# TwoLayerMotorDriver.net
KiCad netlist of a schematic drawn in Altium Designer
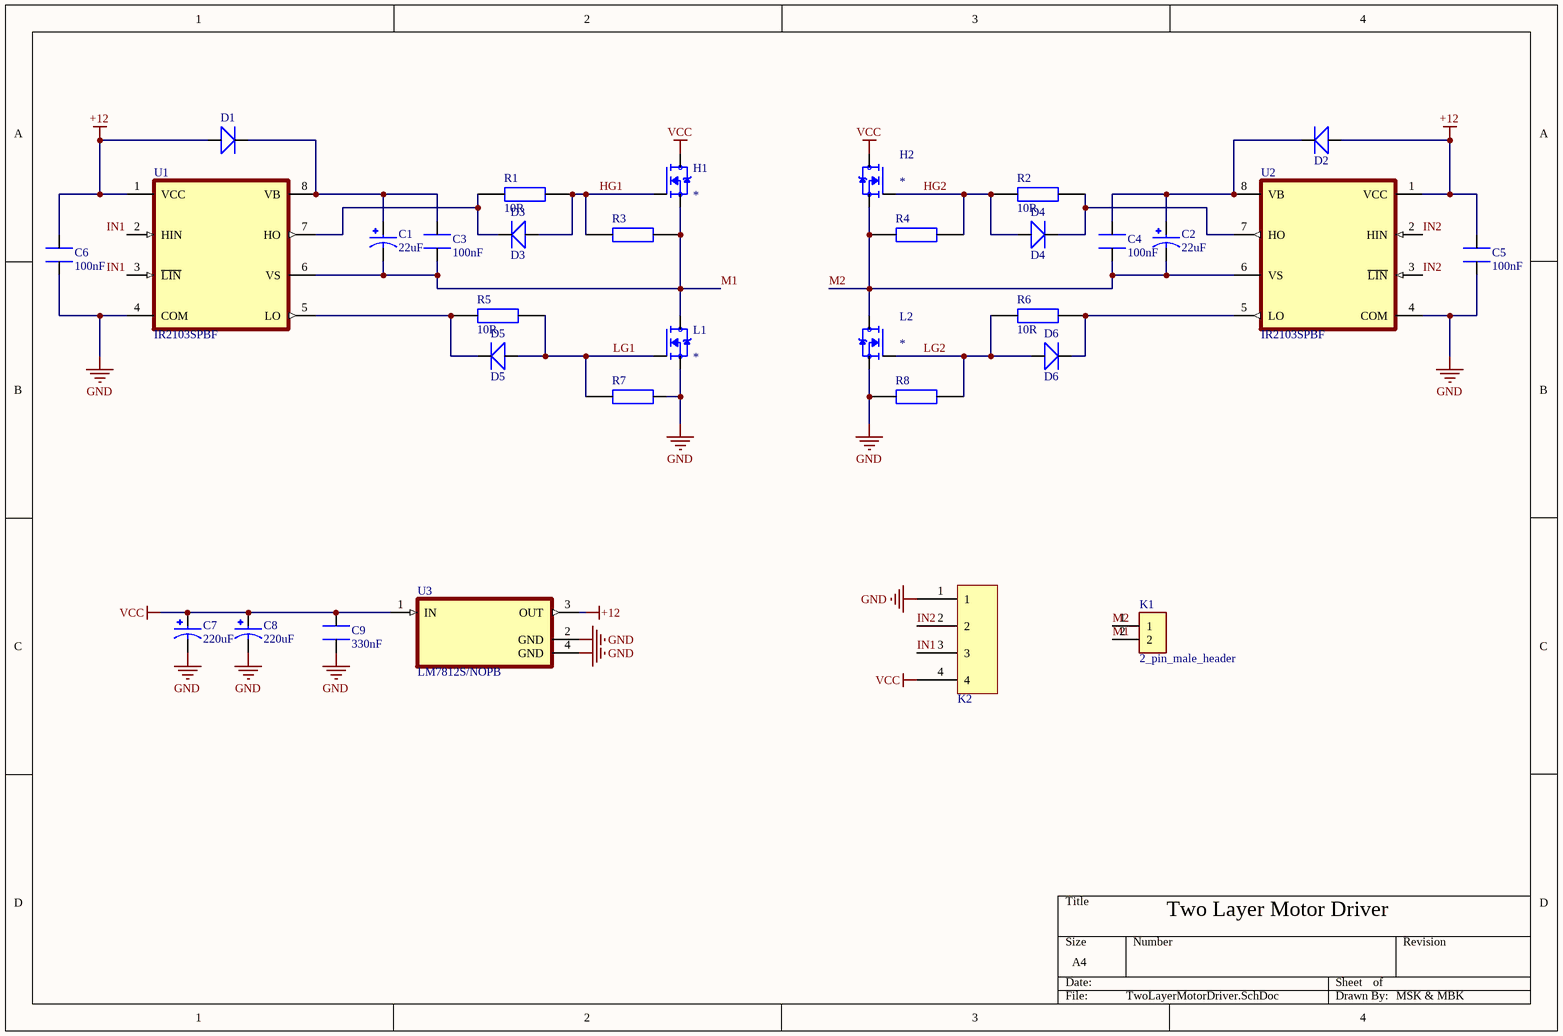
[diagram p0: TwoLayerMotorDriver.SchDoc]

(export (version "E")
  (design (tool "Eeschema 10.0.6"))
  (components
    (comp (ref "C1")
      (value "22uF")
      (footprint "TwoLayerDriverPcbLib:22uF-50V_CAP_EEEFN1H220UR")
      (description "CAP ALUM 22UF 20% 50V SMD")
      (fields (field (name "MF") "Panasonic Electronic Components") (field (name "MP") "EEE-FN1H220UR"))
      (libsource (lib "TwoLayerDriverSchlib") (part "22uF"))
    )
    (comp (ref "C2")
      (value "22uF")
      (footprint "TwoLayerDriverPcbLib:22uF-50V_CAP_EEEFN1H220UR")
      (description "CAP ALUM 22UF 20% 50V SMD")
      (fields (field (name "MF") "Panasonic Electronic Components") (field (name "MP") "EEE-FN1H220UR"))
      (libsource (lib "TwoLayerDriverSchlib") (part "22uF"))
    )
    (comp (ref "C3")
      (value "100nF")
      (footprint "1206 PACKAGE")
      (libsource (lib "Schlib1") (part "100nF 50V SERAMIC CAPACITOR"))
    )
    (comp (ref "C4")
      (value "100nF")
      (footprint "1206 PACKAGE")
      (libsource (lib "Schlib1") (part "100nF 50V SERAMIC CAPACITOR"))
    )
    (comp (ref "C5")
      (value "100nF")
      (footprint "1206 PACKAGE")
      (libsource (lib "Schlib1") (part "100nF 50V SERAMIC CAPACITOR"))
    )
    (comp (ref "C6")
      (value "100nF")
      (footprint "1206 PACKAGE")
      (libsource (lib "Schlib1") (part "100nF 50V SERAMIC CAPACITOR"))
    )
    (comp (ref "C7")
      (value "220uF")
      (footprint "TwoLayerDriverPcbLib:220uF")
      (description "CAP ALUM 220UF 20% 50V SMD")
      (fields (field (name "MF") "Panasonic") (field (name "MP") "EEEFP1H221AL"))
      (libsource (lib "TwoLayerDriverSchlib") (part "220uF"))
    )
    (comp (ref "C8")
      (value "220uF")
      (footprint "TwoLayerDriverPcbLib:220uF")
      (description "CAP ALUM 220UF 20% 50V SMD")
      (fields (field (name "MF") "Panasonic") (field (name "MP") "EEEFP1H221AL"))
      (libsource (lib "TwoLayerDriverSchlib") (part "220uF"))
    )
    (comp (ref "C9")
      (value "330nF")
      (footprint "1206 PACKAGE")
      (description "330nF 50V seramic capacitor 1206 package")
      (libsource (lib "TwoLayerDriverSchlib") (part "330nF"))
    )
    (comp (ref "D1")
      (value "Diode")
      (footprint "FR1M-13")
      (fields (field (name "PART NUMBER") "FR1MDITR-ND"))
      (libsource (lib "Schlib1") (part "FR1MDITR DIODE"))
    )
    (comp (ref "D2")
      (value "Diode")
      (footprint "FR1M-13")
      (fields (field (name "PART NUMBER") "FR1MDITR-ND"))
      (libsource (lib "Schlib1") (part "FR1MDITR DIODE"))
    )
    (comp (ref "D3")
      (value "D3")
      (footprint "FR1M-13")
      (libsource (lib "TwoLayerDriverSchlib") (part "DIODE"))
    )
    (comp (ref "D4")
      (value "D4")
      (footprint "FR1M-13")
      (libsource (lib "TwoLayerDriverSchlib") (part "DIODE"))
    )
    (comp (ref "D5")
      (value "D5")
      (footprint "FR1M-13")
      (libsource (lib "TwoLayerDriverSchlib") (part "DIODE"))
    )
    (comp (ref "D6")
      (value "D6")
      (footprint "FR1M-13")
      (libsource (lib "TwoLayerDriverSchlib") (part "DIODE"))
    )
    (comp (ref "H1")
      (value "IRF3205S_PBF")
      (footprint "3205pbf")
      (fields
        (field (name "MF") "Infineon Technologies")
        (field (name "MP") "IRF3205SPBF")
        (field (name "ALTIUM_VALUE") "*")
      )
      (libsource (lib "TwoLayerDriverSchlib") (part "IRF3205S_PBF"))
    )
    (comp (ref "H2")
      (value "IRF3205S_PBF")
      (footprint "3205pbf")
      (fields
        (field (name "MF") "Infineon Technologies")
        (field (name "MP") "IRF3205SPBF")
        (field (name "ALTIUM_VALUE") "*")
      )
      (libsource (lib "TwoLayerDriverSchlib") (part "IRF3205S_PBF"))
    )
    (comp (ref "K1")
      (value "2_pin_male_header")
      (footprint "TwoLayerDriverPcbLib:2_pin_male_header")
      (description "TERM BLOCK 5.08MM 2POS SIDE ENTY")
      (fields (field (name "MP") "282837-2"))
      (libsource (lib "TwoLayerDriverSchlib") (part "2_pin_male_header"))
    )
    (comp (ref "K2")
      (value "4 Pin Klemens PCB")
      (footprint "4pin Terminal")
      (fields (field (name "DESIGNED BY") "Bora"))
      (libsource (lib "TwoLayerDriverSchlib") (part "4 Pin Klemens PCB"))
    )
    (comp (ref "L1")
      (value "IRF3205S_PBF")
      (footprint "3205pbf")
      (fields
        (field (name "MF") "Infineon Technologies")
        (field (name "MP") "IRF3205SPBF")
        (field (name "ALTIUM_VALUE") "*")
      )
      (libsource (lib "TwoLayerDriverSchlib") (part "IRF3205S_PBF"))
    )
    (comp (ref "L2")
      (value "IRF3205S_PBF")
      (footprint "3205pbf")
      (fields
        (field (name "MF") "Infineon Technologies")
        (field (name "MP") "IRF3205SPBF")
        (field (name "ALTIUM_VALUE") "*")
      )
      (libsource (lib "TwoLayerDriverSchlib") (part "IRF3205S_PBF"))
    )
    (comp (ref "R1")
      (value "10R")
      (footprint "1206 PACKAGE")
      (fields
        (field (name "MOUSER PART NUMBER") "71-CRCW12061K00FKEAH")
        (field (name "MANUFACTURER_PART_NUMBER") "CRCW12061K00FKEAHP")
      )
      (libsource (lib "TwoLayerDriverSchlib") (part "10 1/4W"))
    )
    (comp (ref "R2")
      (value "10R")
      (footprint "1206 PACKAGE")
      (fields
        (field (name "MOUSER PART NUMBER") "71-CRCW12061K00FKEAH")
        (field (name "MANUFACTURER_PART_NUMBER") "CRCW12061K00FKEAHP")
      )
      (libsource (lib "TwoLayerDriverSchlib") (part "10 1/4W"))
    )
    (comp (ref "R3")
      (value "CRCW12061K00FKEAHP")
      (footprint "1206 PACKAGE")
      (fields (field (name "MOUSER PART NUMBER") "71-CRCW12061K00FKEAH"))
      (libsource (lib "TwoLayerDriverSchlib") (part "1K 1/4W"))
    )
    (comp (ref "R4")
      (value "CRCW12061K00FKEAHP")
      (footprint "1206 PACKAGE")
      (fields (field (name "MOUSER PART NUMBER") "71-CRCW12061K00FKEAH"))
      (libsource (lib "TwoLayerDriverSchlib") (part "1K 1/4W"))
    )
    (comp (ref "R5")
      (value "10R")
      (footprint "1206 PACKAGE")
      (fields
        (field (name "MOUSER PART NUMBER") "71-CRCW12061K00FKEAH")
        (field (name "MANUFACTURER_PART_NUMBER") "CRCW12061K00FKEAHP")
      )
      (libsource (lib "TwoLayerDriverSchlib") (part "10 1/4W"))
    )
    (comp (ref "R6")
      (value "10R")
      (footprint "1206 PACKAGE")
      (fields
        (field (name "MOUSER PART NUMBER") "71-CRCW12061K00FKEAH")
        (field (name "MANUFACTURER_PART_NUMBER") "CRCW12061K00FKEAHP")
      )
      (libsource (lib "TwoLayerDriverSchlib") (part "10 1/4W"))
    )
    (comp (ref "R7")
      (value "CRCW12061K00FKEAHP")
      (footprint "1206 PACKAGE")
      (fields (field (name "MOUSER PART NUMBER") "71-CRCW12061K00FKEAH"))
      (libsource (lib "TwoLayerDriverSchlib") (part "1K 1/4W"))
    )
    (comp (ref "R8")
      (value "CRCW12061K00FKEAHP")
      (footprint "1206 PACKAGE")
      (fields (field (name "MOUSER PART NUMBER") "71-CRCW12061K00FKEAH"))
      (libsource (lib "TwoLayerDriverSchlib") (part "1K 1/4W"))
    )
    (comp (ref "U1")
      (value "IR2103SPBF")
      (footprint "TwoLayerDriverPcbLib:2103SMD-8SOIC")
      (fields (field (name "MF") "Infineon"))
      (libsource (lib "TwoLayerDriverSchlib") (part "IR2103SPBF"))
    )
    (comp (ref "U2")
      (value "IR2103SPBF")
      (footprint "TwoLayerDriverPcbLib:2103SMD-8SOIC")
      (fields (field (name "MF") "Infineon"))
      (libsource (lib "") (part "IR2103SPBF_1"))
    )
    (comp (ref "U3")
      (value "LM7812S/NOPB")
      (footprint "TwoLayerDriverPcbLib:lm7812")
      (description "1.5-A, 30-V, linear voltage regulator 3-DDPAK/TO-263 0 to 125")
      (fields (field (name "MF") "Texas Instruments"))
      (libsource (lib "TwoLayerDriverSchlib") (part "LM7812S/NOPB"))
    )
  )
  (nets
    (net (code "1") (name "+12") (class "Default")
      (node (ref "C5") (pin "2") (pinfunction "2_2") (pintype "passive"))
      (node (ref "C6") (pin "2") (pinfunction "2_2") (pintype "passive"))
      (node (ref "D1") (pin "0") (pinfunction "0_0") (pintype "passive"))
      (node (ref "D2") (pin "0") (pinfunction "0_0") (pintype "passive"))
      (node (ref "U1") (pin "1") (pinfunction "VCC_1") (pintype "power_in"))
      (node (ref "U2") (pin "1") (pinfunction "VCC_1") (pintype "power_in"))
      (node (ref "U3") (pin "3") (pinfunction "OUT_3") (pintype "output"))
    )
    (net (code "2") (name "/HG1") (class "Default")
      (node (ref "D3") (pin "1") (pinfunction "1_1") (pintype "passive"))
      (node (ref "H1") (pin "1") (pinfunction "G_1") (pintype "passive"))
      (node (ref "R1") (pin "2") (pinfunction "2_2") (pintype "passive"))
      (node (ref "R3") (pin "1") (pinfunction "1_1") (pintype "passive"))
    )
    (net (code "3") (name "/HG2") (class "Default")
      (node (ref "D4") (pin "1") (pinfunction "1_1") (pintype "passive"))
      (node (ref "H2") (pin "1") (pinfunction "G_1") (pintype "passive"))
      (node (ref "R2") (pin "1") (pinfunction "1_1") (pintype "passive"))
      (node (ref "R4") (pin "2") (pinfunction "2_2") (pintype "passive"))
    )
    (net (code "4") (name "/IN1") (class "Default")
      (node (ref "K2") (pin "3") (pinfunction "3_3") (pintype "passive"))
      (node (ref "U1") (pin "2") (pinfunction "HIN_2") (pintype "input"))
      (node (ref "U1") (pin "3") (pinfunction "~{LIN}_3") (pintype "input"))
    )
    (net (code "5") (name "/IN2") (class "Default")
      (node (ref "K2") (pin "2") (pinfunction "2_2") (pintype "passive"))
      (node (ref "U2") (pin "2") (pinfunction "HIN_2") (pintype "input"))
      (node (ref "U2") (pin "3") (pinfunction "~{LIN}_3") (pintype "input"))
    )
    (net (code "6") (name "/LG1") (class "Default")
      (node (ref "D5") (pin "1") (pinfunction "1_1") (pintype "passive"))
      (node (ref "L1") (pin "1") (pinfunction "G_1") (pintype "passive"))
      (node (ref "R5") (pin "2") (pinfunction "2_2") (pintype "passive"))
      (node (ref "R7") (pin "1") (pinfunction "1_1") (pintype "passive"))
    )
    (net (code "7") (name "/LG2") (class "Default")
      (node (ref "D6") (pin "1") (pinfunction "1_1") (pintype "passive"))
      (node (ref "L2") (pin "1") (pinfunction "G_1") (pintype "passive"))
      (node (ref "R6") (pin "1") (pinfunction "1_1") (pintype "passive"))
      (node (ref "R8") (pin "2") (pinfunction "2_2") (pintype "passive"))
    )
    (net (code "8") (name "/M1") (class "Default")
      (node (ref "C1") (pin "2") (pinfunction "2_2") (pintype "passive"))
      (node (ref "C3") (pin "1") (pinfunction "1_1") (pintype "passive"))
      (node (ref "H1") (pin "3") (pinfunction "S_3") (pintype "passive"))
      (node (ref "K1") (pin "2") (pinfunction "2_2") (pintype "passive"))
      (node (ref "L1") (pin "2") (pinfunction "D_2") (pintype "passive"))
      (node (ref "R3") (pin "2") (pinfunction "2_2") (pintype "passive"))
      (node (ref "U1") (pin "6") (pinfunction "VS_6") (pintype "power_in"))
    )
    (net (code "9") (name "/M2") (class "Default")
      (node (ref "C2") (pin "2") (pinfunction "2_2") (pintype "passive"))
      (node (ref "C4") (pin "1") (pinfunction "1_1") (pintype "passive"))
      (node (ref "H2") (pin "3") (pinfunction "S_3") (pintype "passive"))
      (node (ref "K1") (pin "1") (pinfunction "1_1") (pintype "passive"))
      (node (ref "L2") (pin "2") (pinfunction "D_2") (pintype "passive"))
      (node (ref "R4") (pin "1") (pinfunction "1_1") (pintype "passive"))
      (node (ref "U2") (pin "6") (pinfunction "VS_6") (pintype "power_in"))
    )
    (net (code "10") (name "GND") (class "Default")
      (node (ref "C5") (pin "1") (pinfunction "1_1") (pintype "passive"))
      (node (ref "C6") (pin "1") (pinfunction "1_1") (pintype "passive"))
      (node (ref "C7") (pin "2") (pinfunction "2_2") (pintype "passive"))
      (node (ref "C8") (pin "2") (pinfunction "2_2") (pintype "passive"))
      (node (ref "C9") (pin "2") (pinfunction "2_2") (pintype "passive"))
      (node (ref "K2") (pin "1") (pinfunction "1_1") (pintype "passive"))
      (node (ref "L1") (pin "3") (pinfunction "S_3") (pintype "passive"))
      (node (ref "L2") (pin "3") (pinfunction "S_3") (pintype "passive"))
      (node (ref "R7") (pin "2") (pinfunction "2_2") (pintype "passive"))
      (node (ref "R8") (pin "1") (pinfunction "1_1") (pintype "passive"))
      (node (ref "U1") (pin "4") (pinfunction "COM_4") (pintype "passive"))
      (node (ref "U2") (pin "4") (pinfunction "COM_4") (pintype "passive"))
      (node (ref "U3") (pin "2") (pinfunction "GND_2") (pintype "power_in"))
      (node (ref "U3") (pin "4") (pinfunction "GND_4") (pintype "power_in"))
    )
    (net (code "11") (name "Net-(U1-HO)") (class "Default")
      (node (ref "D3") (pin "2") (pinfunction "2_2") (pintype "passive"))
      (node (ref "R1") (pin "1") (pinfunction "1_1") (pintype "passive"))
      (node (ref "U1") (pin "7") (pinfunction "HO_7") (pintype "output"))
    )
    (net (code "12") (name "Net-(U1-LO)") (class "Default")
      (node (ref "D5") (pin "2") (pinfunction "2_2") (pintype "passive"))
      (node (ref "R5") (pin "1") (pinfunction "1_1") (pintype "passive"))
      (node (ref "U1") (pin "5") (pinfunction "LO_5") (pintype "output"))
    )
    (net (code "13") (name "Net-(U1-VB)") (class "Default")
      (node (ref "C1") (pin "1") (pinfunction "1_1") (pintype "passive"))
      (node (ref "C3") (pin "2") (pinfunction "2_2") (pintype "passive"))
      (node (ref "D1") (pin "1") (pinfunction "1_1") (pintype "passive"))
      (node (ref "U1") (pin "8") (pinfunction "VB_8") (pintype "power_in"))
    )
    (net (code "14") (name "Net-(U2-HO)") (class "Default")
      (node (ref "D4") (pin "2") (pinfunction "2_2") (pintype "passive"))
      (node (ref "R2") (pin "2") (pinfunction "2_2") (pintype "passive"))
      (node (ref "U2") (pin "7") (pinfunction "HO_7") (pintype "output"))
    )
    (net (code "15") (name "Net-(U2-LO)") (class "Default")
      (node (ref "D6") (pin "2") (pinfunction "2_2") (pintype "passive"))
      (node (ref "R6") (pin "2") (pinfunction "2_2") (pintype "passive"))
      (node (ref "U2") (pin "5") (pinfunction "LO_5") (pintype "output"))
    )
    (net (code "16") (name "Net-(U2-VB)") (class "Default")
      (node (ref "C2") (pin "1") (pinfunction "1_1") (pintype "passive"))
      (node (ref "C4") (pin "2") (pinfunction "2_2") (pintype "passive"))
      (node (ref "D2") (pin "1") (pinfunction "1_1") (pintype "passive"))
      (node (ref "U2") (pin "8") (pinfunction "VB_8") (pintype "power_in"))
    )
    (net (code "17") (name "VCC") (class "Default")
      (node (ref "C7") (pin "1") (pinfunction "1_1") (pintype "passive"))
      (node (ref "C8") (pin "1") (pinfunction "1_1") (pintype "passive"))
      (node (ref "C9") (pin "1") (pinfunction "1_1") (pintype "passive"))
      (node (ref "H1") (pin "2") (pinfunction "D_2") (pintype "passive"))
      (node (ref "H2") (pin "2") (pinfunction "D_2") (pintype "passive"))
      (node (ref "K2") (pin "4") (pinfunction "4_4") (pintype "passive"))
      (node (ref "U3") (pin "1") (pinfunction "IN_1") (pintype "input"))
    )
  )
)
